# Dataflow.net
KiCad netlist of a schematic drawn in Altium Designer
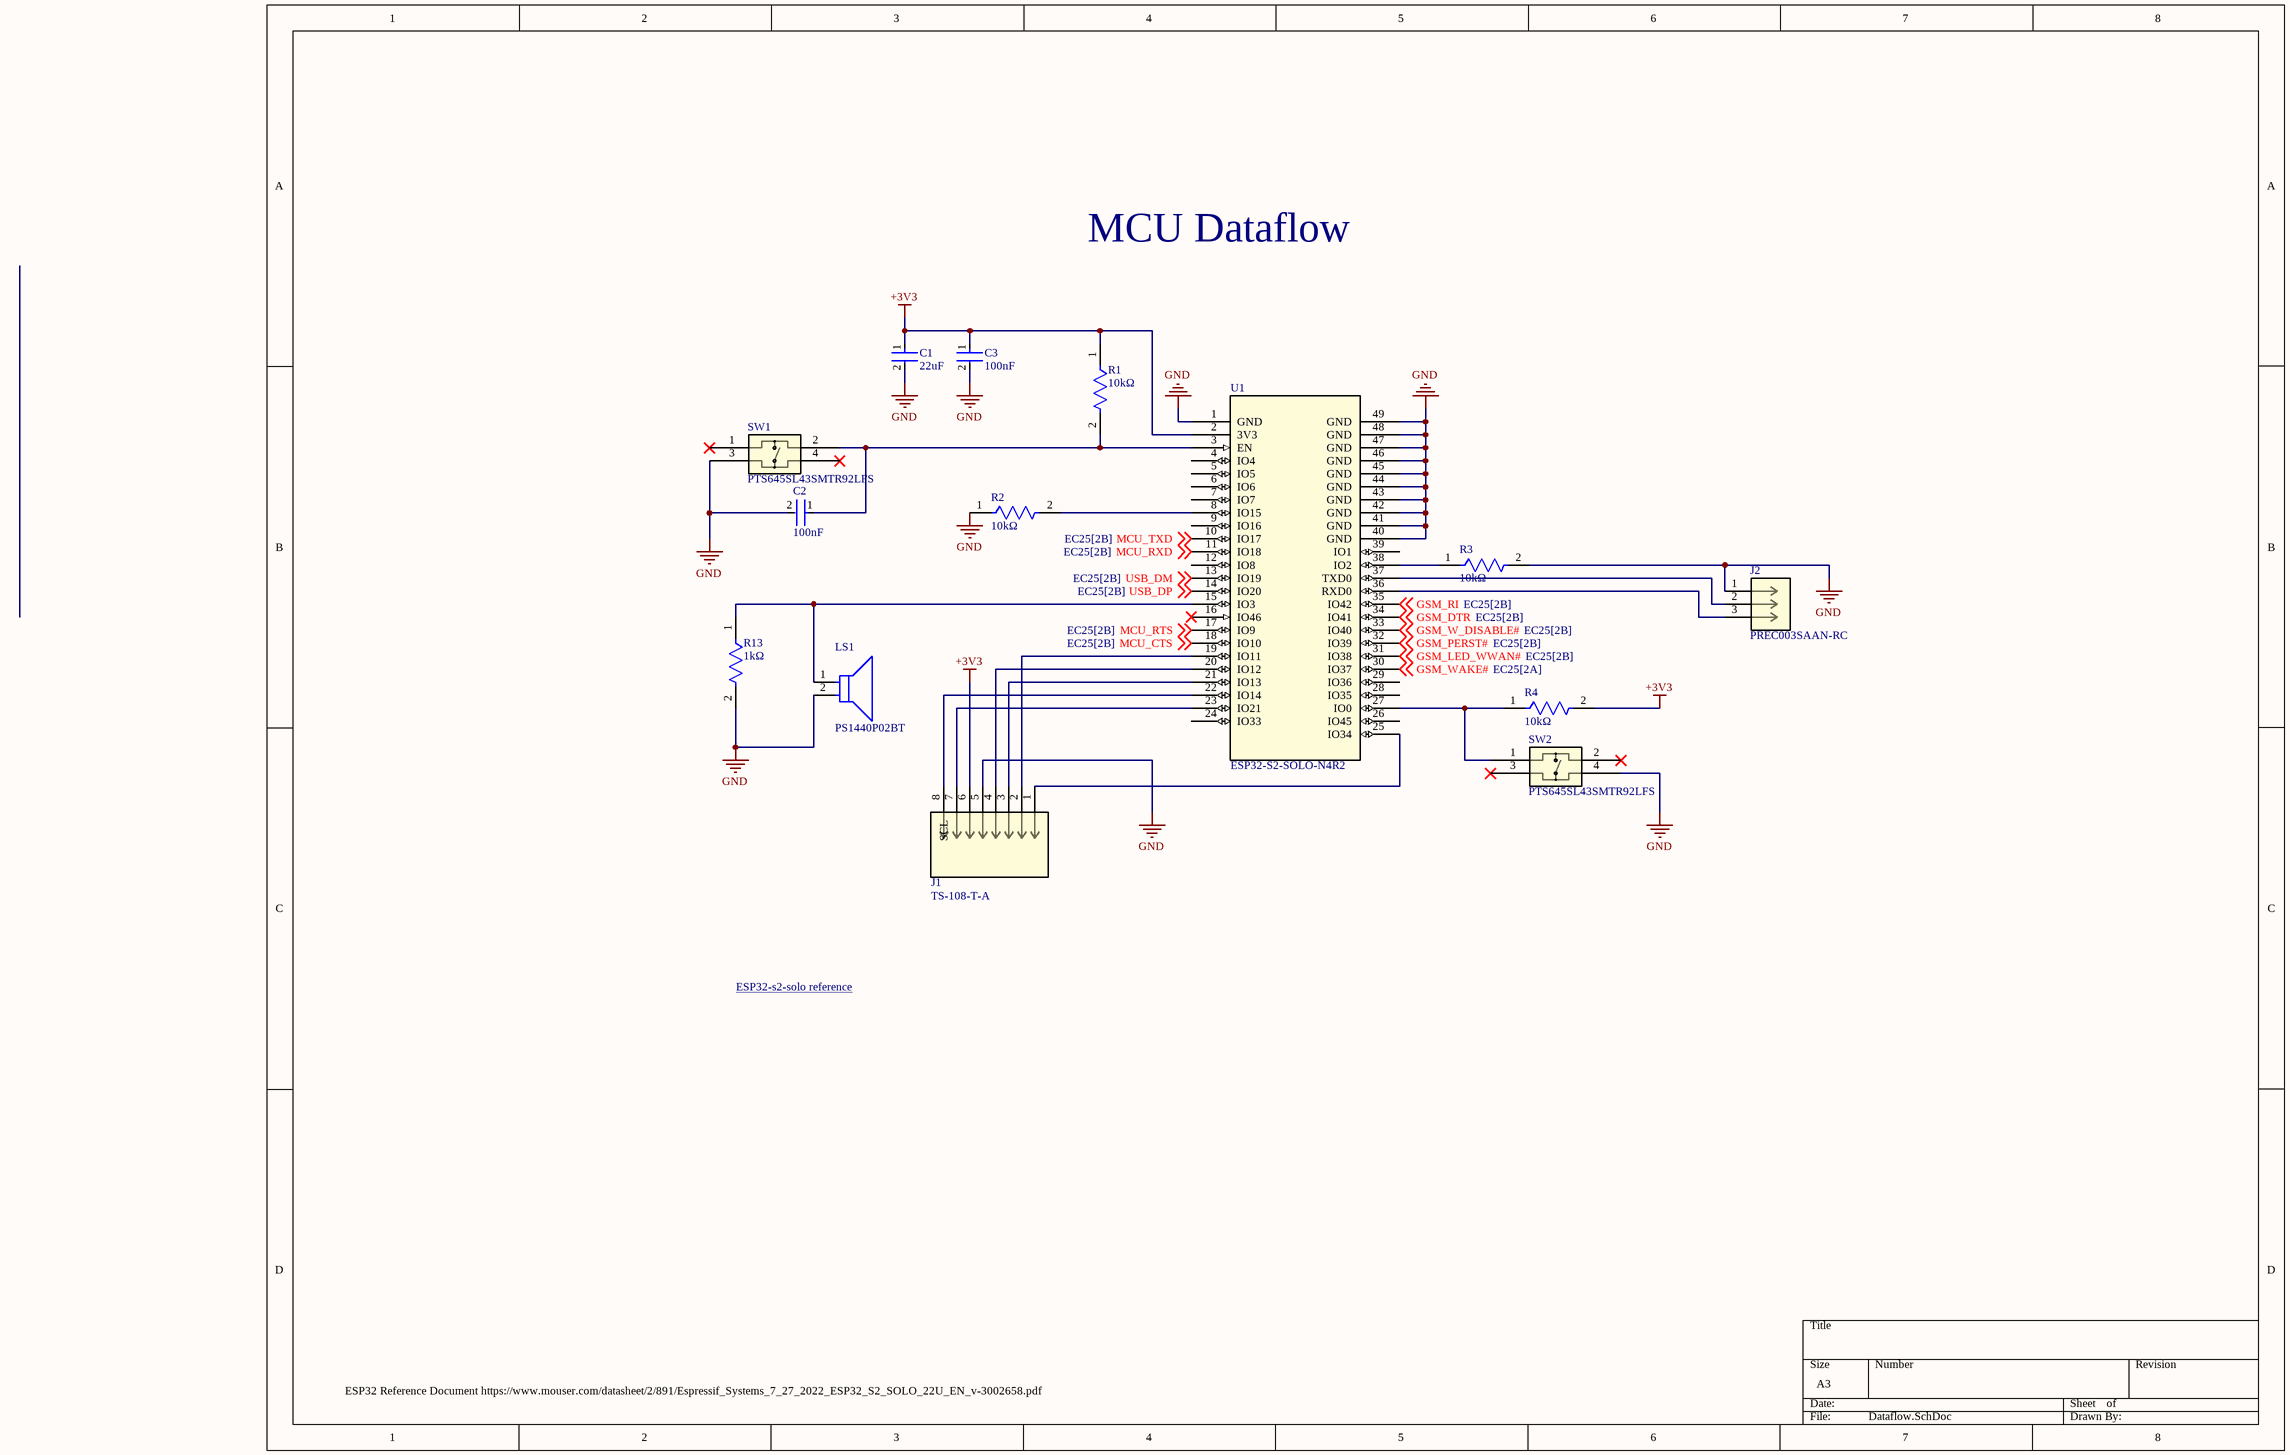
[diagram p0: Dataflow.SchDoc]

(export (version "E")
  (design (tool "Eeschema 10.0.6"))
  (components
    (comp (ref "C1")
      (value "22uF")
      (footprint "FP-CL21-IPC_C")
      (description "CL21A226MAYNNNE CL21 Series 0805 22uF 25V ±20% Tolerance X5R Multilayer Ceramic Chip Capacitor")
      (libsource (lib "Altium Content Vault") (part "b4654b650e69147ec39a6b967a45e02"))
    )
    (comp (ref "C2")
      (value "100nF")
      (footprint "FP-CL21-IPC_C")
      (description "CL21B104KACNNNC CL21 Series 0805 100nF 25V ±10% Tolerance X7R Multilayer Ceramic Chip Capacitor")
      (fields (field (name "VOLTAGE") "25V") (field (name "TOLERANCE") "10%"))
      (libsource (lib "Altium Content Vault") (part "b4654b650e69147ec39a6b967a45e02"))
    )
    (comp (ref "C3")
      (value "100nF")
      (footprint "FP-CL21-IPC_C")
      (description "CL21B104KACNNNC CL21 Series 0805 100nF 25V ±10% Tolerance X7R Multilayer Ceramic Chip Capacitor")
      (fields (field (name "VOLTAGE") "25V") (field (name "TOLERANCE") "10%"))
      (libsource (lib "Altium Content Vault") (part "b4654b650e69147ec39a6b967a45e02"))
    )
    (comp (ref "J1")
      (value "TS-108-T-A")
      (footprint "CON8_1X8_TU_HTS_SAI")
      (description "No Description Available")
      (libsource (lib "TS-108-T-A") (part "TS-108-T-A"))
    )
    (comp (ref "J2")
      (value "PREC003SAAN-RC")
      (footprint "CONN_PREC003SAAN-RC_SUL")
      (description "No Description Available")
      (libsource (lib "PREC003SAAN-RC") (part "PREC003SAAN-RC"))
    )
    (comp (ref "LS1")
      (value "PS1440P02BT")
      (footprint "FP-PS1440P02BT-MFG")
      (description "AUDIO PIEZO TRANSDUCER 30V TH")
      (libsource (lib "Altium Content Vault") (part "5f581d31613f872430949aa526fd155"))
    )
    (comp (ref "R1")
      (value "10kΩ")
      (footprint "FP-CRGP2512-IPC_C")
      (description "CRGP2512F10K CRGP 2512 10K 1%")
      (fields (field (name "MANUFACTURER") "TE") (field (name "MANUFACTURER PART NUMBER") "CRGP2512F10K"))
      (libsource (lib "Altium Content Vault") (part "1029c3af85768c4190bb7ad29bc67b5"))
    )
    (comp (ref "R2")
      (value "10kΩ")
      (footprint "FP-CRGP2512-IPC_C")
      (description "CRGP2512F10K CRGP 2512 10K 1%")
      (fields (field (name "MANUFACTURER") "TE") (field (name "MANUFACTURER PART NUMBER") "CRGP2512F10K"))
      (libsource (lib "Altium Content Vault") (part "1029c3af85768c4190bb7ad29bc67b5"))
    )
    (comp (ref "R3")
      (value "10kΩ")
      (footprint "FP-CRGP2512-IPC_C")
      (description "CRGP2512F10K CRGP 2512 10K 1%")
      (fields (field (name "MANUFACTURER") "TE") (field (name "MANUFACTURER PART NUMBER") "CRGP2512F10K"))
      (libsource (lib "Altium Content Vault") (part "1029c3af85768c4190bb7ad29bc67b5"))
    )
    (comp (ref "R4")
      (value "10kΩ")
      (footprint "FP-CRGP2512-IPC_C")
      (description "CRGP2512F10K CRGP 2512 10K 1%")
      (fields (field (name "MANUFACTURER") "TE") (field (name "MANUFACTURER PART NUMBER") "CRGP2512F10K"))
      (libsource (lib "Altium Content Vault") (part "1029c3af85768c4190bb7ad29bc67b5"))
    )
    (comp (ref "R13")
      (value "1kΩ")
      (footprint "FP-CRGP2512-IPC_C")
      (description "CRGP2512F1K0 Res, 1K, 1%, 2W, 2512, Thick Film")
      (fields (field (name "MANUFACTURER") "TE") (field (name "MANUFACTURER PART NUMBER") "CRGP2512F1K0"))
      (libsource (lib "Altium Content Vault") (part "1029c3af85768c4190bb7ad29bc67b5"))
    )
    (comp (ref "SW1")
      (value "PTS645SL43SMTR92LFS")
      (footprint "PTS645SL43SMTR92LFS_CNK")
      (description "No Description Available")
      (libsource (lib "PTS645SL43SMTR92LFS") (part "PTS645SL43SMTR92LFS"))
    )
    (comp (ref "SW2")
      (value "PTS645SL43SMTR92LFS")
      (footprint "PTS645SL43SMTR92LFS_CNK")
      (description "No Description Available")
      (libsource (lib "PTS645SL43SMTR92LFS") (part "PTS645SL43SMTR92LFS"))
    )
    (comp (ref "U1")
      (value "ESP32-S2-SOLO-N4R2")
      (footprint "MOD41_ESP32-S2-SOLO_EXP")
      (description "No Description Available")
      (libsource (lib "ESP32-S2-SOLO-N4R2") (part "ESP32-S2-SOLO-N4R2"))
    )
  )
  (nets
    (net (code "1") (name "+3V3") (class "Default")
      (node (ref "C1") (pin "1") (pinfunction "1_1") (pintype "passive"))
      (node (ref "C3") (pin "1") (pinfunction "1_1") (pintype "passive"))
      (node (ref "J1") (pin "6") (pinfunction "+3V3_6") (pintype "passive"))
      (node (ref "R1") (pin "1") (pinfunction "1_1") (pintype "passive"))
      (node (ref "R4") (pin "2") (pinfunction "2_2") (pintype "passive"))
      (node (ref "U1") (pin "2") (pinfunction "3V3_2") (pintype "power_in"))
    )
    (net (code "2") (name "GND") (class "Default")
      (node (ref "C1") (pin "2") (pinfunction "2_2") (pintype "passive"))
      (node (ref "C2") (pin "2") (pinfunction "2_2") (pintype "passive"))
      (node (ref "C3") (pin "2") (pinfunction "2_2") (pintype "passive"))
      (node (ref "J1") (pin "5") (pinfunction "GND_5") (pintype "passive"))
      (node (ref "J2") (pin "1") (pinfunction "1_1") (pintype "passive"))
      (node (ref "LS1") (pin "2") (pinfunction "2_2") (pintype "passive"))
      (node (ref "R13") (pin "2") (pinfunction "2_2") (pintype "passive"))
      (node (ref "R2") (pin "1") (pinfunction "1_1") (pintype "passive"))
      (node (ref "R3") (pin "2") (pinfunction "2_2") (pintype "passive"))
      (node (ref "SW1") (pin "3") (pinfunction "3_3") (pintype "passive"))
      (node (ref "SW2") (pin "4") (pinfunction "4_4") (pintype "passive"))
      (node (ref "U1") (pin "1") (pinfunction "GND_1") (pintype "power_in"))
      (node (ref "U1") (pin "40") (pinfunction "GND_40") (pintype "power_in"))
      (node (ref "U1") (pin "41") (pinfunction "GND_41") (pintype "power_in"))
      (node (ref "U1") (pin "42") (pinfunction "GND_42") (pintype "power_in"))
      (node (ref "U1") (pin "43") (pinfunction "GND_43") (pintype "power_in"))
      (node (ref "U1") (pin "44") (pinfunction "GND_44") (pintype "power_in"))
      (node (ref "U1") (pin "45") (pinfunction "GND_45") (pintype "power_in"))
      (node (ref "U1") (pin "46") (pinfunction "GND_46") (pintype "power_in"))
      (node (ref "U1") (pin "47") (pinfunction "GND_47") (pintype "power_in"))
      (node (ref "U1") (pin "48") (pinfunction "GND_48") (pintype "power_in"))
      (node (ref "U1") (pin "49") (pinfunction "GND_49") (pintype "power_in"))
    )
    (net (code "3") (name "GSM_DTR") (class "Default")
      (node (ref "U1") (pin "34") (pinfunction "IO41_34") (pintype "bidirectional"))
    )
    (net (code "4") (name "GSM_LED_WWAN#") (class "Default")
      (node (ref "U1") (pin "31") (pinfunction "IO38_31") (pintype "bidirectional"))
    )
    (net (code "5") (name "GSM_PERST#") (class "Default")
      (node (ref "U1") (pin "32") (pinfunction "IO39_32") (pintype "bidirectional"))
    )
    (net (code "6") (name "GSM_RI") (class "Default")
      (node (ref "U1") (pin "35") (pinfunction "IO42_35") (pintype "bidirectional"))
    )
    (net (code "7") (name "GSM_WAKE#") (class "Default")
      (node (ref "U1") (pin "30") (pinfunction "IO37_30") (pintype "bidirectional"))
    )
    (net (code "8") (name "GSM_W_DISABLE#") (class "Default")
      (node (ref "U1") (pin "33") (pinfunction "IO40_33") (pintype "bidirectional"))
    )
    (net (code "9") (name "MCU_CTS") (class "Default")
      (node (ref "U1") (pin "18") (pinfunction "IO10_18") (pintype "bidirectional"))
    )
    (net (code "10") (name "MCU_RTS") (class "Default")
      (node (ref "U1") (pin "17") (pinfunction "IO9_17") (pintype "bidirectional"))
    )
    (net (code "11") (name "MCU_RXD") (class "Default")
      (node (ref "U1") (pin "11") (pinfunction "IO18_11") (pintype "bidirectional"))
    )
    (net (code "12") (name "MCU_TXD") (class "Default")
      (node (ref "U1") (pin "10") (pinfunction "IO17_10") (pintype "bidirectional"))
    )
    (net (code "13") (name "Net-(J1-CS)") (class "Default")
      (node (ref "J1") (pin "1") (pinfunction "CS_1") (pintype "passive"))
      (node (ref "U1") (pin "25") (pinfunction "IO34_25") (pintype "bidirectional"))
    )
    (net (code "14") (name "Net-(J1-MISO)") (class "Default")
      (node (ref "J1") (pin "3") (pinfunction "MISO_3") (pintype "passive"))
      (node (ref "U1") (pin "21") (pinfunction "IO13_21") (pintype "bidirectional"))
    )
    (net (code "15") (name "Net-(J1-MOSI)") (class "Default")
      (node (ref "J1") (pin "2") (pinfunction "MOSI_2") (pintype "passive"))
      (node (ref "U1") (pin "19") (pinfunction "IO11_19") (pintype "bidirectional"))
    )
    (net (code "16") (name "Net-(J1-SCL)") (class "Default")
      (node (ref "J1") (pin "8") (pinfunction "SCL_8") (pintype "passive"))
      (node (ref "U1") (pin "22") (pinfunction "IO14_22") (pintype "bidirectional"))
    )
    (net (code "17") (name "Net-(J1-SCLK)") (class "Default")
      (node (ref "J1") (pin "4") (pinfunction "SCLK_4") (pintype "passive"))
      (node (ref "U1") (pin "20") (pinfunction "IO12_20") (pintype "bidirectional"))
    )
    (net (code "18") (name "Net-(J1-SDA)") (class "Default")
      (node (ref "J1") (pin "7") (pinfunction "SDA_7") (pintype "passive"))
      (node (ref "U1") (pin "23") (pinfunction "IO21_23") (pintype "bidirectional"))
    )
    (net (code "19") (name "Net-(U1-EN)") (class "Default")
      (node (ref "C2") (pin "1") (pinfunction "1_1") (pintype "passive"))
      (node (ref "R1") (pin "2") (pinfunction "2_2") (pintype "passive"))
      (node (ref "SW1") (pin "2") (pinfunction "2_2") (pintype "passive"))
      (node (ref "U1") (pin "3") (pinfunction "EN_3") (pintype "input"))
    )
    (net (code "20") (name "Net-(U1-IO0)") (class "Default")
      (node (ref "R4") (pin "1") (pinfunction "1_1") (pintype "passive"))
      (node (ref "SW2") (pin "1") (pinfunction "1_1") (pintype "passive"))
      (node (ref "U1") (pin "27") (pinfunction "IO0_27") (pintype "bidirectional"))
    )
    (net (code "21") (name "Net-(U1-IO2)") (class "Default")
      (node (ref "R3") (pin "1") (pinfunction "1_1") (pintype "passive"))
      (node (ref "U1") (pin "38") (pinfunction "IO2_38") (pintype "bidirectional"))
    )
    (net (code "22") (name "Net-(U1-IO3)") (class "Default")
      (node (ref "LS1") (pin "1") (pinfunction "1_1") (pintype "passive"))
      (node (ref "R13") (pin "1") (pinfunction "1_1") (pintype "passive"))
      (node (ref "U1") (pin "15") (pinfunction "IO3_15") (pintype "bidirectional"))
    )
    (net (code "23") (name "Net-(U1-IO15)") (class "Default")
      (node (ref "R2") (pin "2") (pinfunction "2_2") (pintype "passive"))
      (node (ref "U1") (pin "8") (pinfunction "IO15_8") (pintype "bidirectional"))
    )
    (net (code "24") (name "Net-(U1-RXD0)") (class "Default")
      (node (ref "J2") (pin "3") (pinfunction "3_3") (pintype "passive"))
      (node (ref "U1") (pin "36") (pinfunction "RXD0_36") (pintype "bidirectional"))
    )
    (net (code "25") (name "Net-(U1-TXD0)") (class "Default")
      (node (ref "J2") (pin "2") (pinfunction "2_2") (pintype "passive"))
      (node (ref "U1") (pin "37") (pinfunction "TXD0_37") (pintype "bidirectional"))
    )
    (net (code "26") (name "USB_DM") (class "Default")
      (node (ref "U1") (pin "13") (pinfunction "IO19_13") (pintype "bidirectional"))
    )
    (net (code "27") (name "USB_DP") (class "Default")
      (node (ref "U1") (pin "14") (pinfunction "IO20_14") (pintype "bidirectional"))
    )
    (net (code "28") (name "unconnected-(SW1-Pad1)") (class "Default")
      (node (ref "SW1") (pin "1") (pinfunction "1_1") (pintype "passive+no_connect"))
    )
    (net (code "29") (name "unconnected-(SW1-Pad4)") (class "Default")
      (node (ref "SW1") (pin "4") (pinfunction "4_4") (pintype "passive+no_connect"))
    )
    (net (code "30") (name "unconnected-(SW2-Pad2)") (class "Default")
      (node (ref "SW2") (pin "2") (pinfunction "2_2") (pintype "passive+no_connect"))
    )
    (net (code "31") (name "unconnected-(SW2-Pad3)") (class "Default")
      (node (ref "SW2") (pin "3") (pinfunction "3_3") (pintype "passive+no_connect"))
    )
    (net (code "32") (name "unconnected-(U1-IO1-Pad39)") (class "Default")
      (node (ref "U1") (pin "39") (pinfunction "IO1_39") (pintype "bidirectional"))
    )
    (net (code "33") (name "unconnected-(U1-IO4-Pad4)") (class "Default")
      (node (ref "U1") (pin "4") (pinfunction "IO4_4") (pintype "bidirectional"))
    )
    (net (code "34") (name "unconnected-(U1-IO5-Pad5)") (class "Default")
      (node (ref "U1") (pin "5") (pinfunction "IO5_5") (pintype "bidirectional"))
    )
    (net (code "35") (name "unconnected-(U1-IO6-Pad6)") (class "Default")
      (node (ref "U1") (pin "6") (pinfunction "IO6_6") (pintype "bidirectional"))
    )
    (net (code "36") (name "unconnected-(U1-IO7-Pad7)") (class "Default")
      (node (ref "U1") (pin "7") (pinfunction "IO7_7") (pintype "bidirectional"))
    )
    (net (code "37") (name "unconnected-(U1-IO8-Pad12)") (class "Default")
      (node (ref "U1") (pin "12") (pinfunction "IO8_12") (pintype "bidirectional"))
    )
    (net (code "38") (name "unconnected-(U1-IO16-Pad9)") (class "Default")
      (node (ref "U1") (pin "9") (pinfunction "IO16_9") (pintype "bidirectional"))
    )
    (net (code "39") (name "unconnected-(U1-IO33-Pad24)") (class "Default")
      (node (ref "U1") (pin "24") (pinfunction "IO33_24") (pintype "bidirectional"))
    )
    (net (code "40") (name "unconnected-(U1-IO35-Pad28)") (class "Default")
      (node (ref "U1") (pin "28") (pinfunction "IO35_28") (pintype "bidirectional"))
    )
    (net (code "41") (name "unconnected-(U1-IO36-Pad29)") (class "Default")
      (node (ref "U1") (pin "29") (pinfunction "IO36_29") (pintype "bidirectional"))
    )
    (net (code "42") (name "unconnected-(U1-IO45-Pad26)") (class "Default")
      (node (ref "U1") (pin "26") (pinfunction "IO45_26") (pintype "bidirectional"))
    )
    (net (code "43") (name "unconnected-(U1-IO46-Pad16)") (class "Default")
      (node (ref "U1") (pin "16") (pinfunction "IO46_16") (pintype "input+no_connect"))
    )
  )
)
